# Interface_board.net
KiCad netlist of a schematic drawn in EAGLE
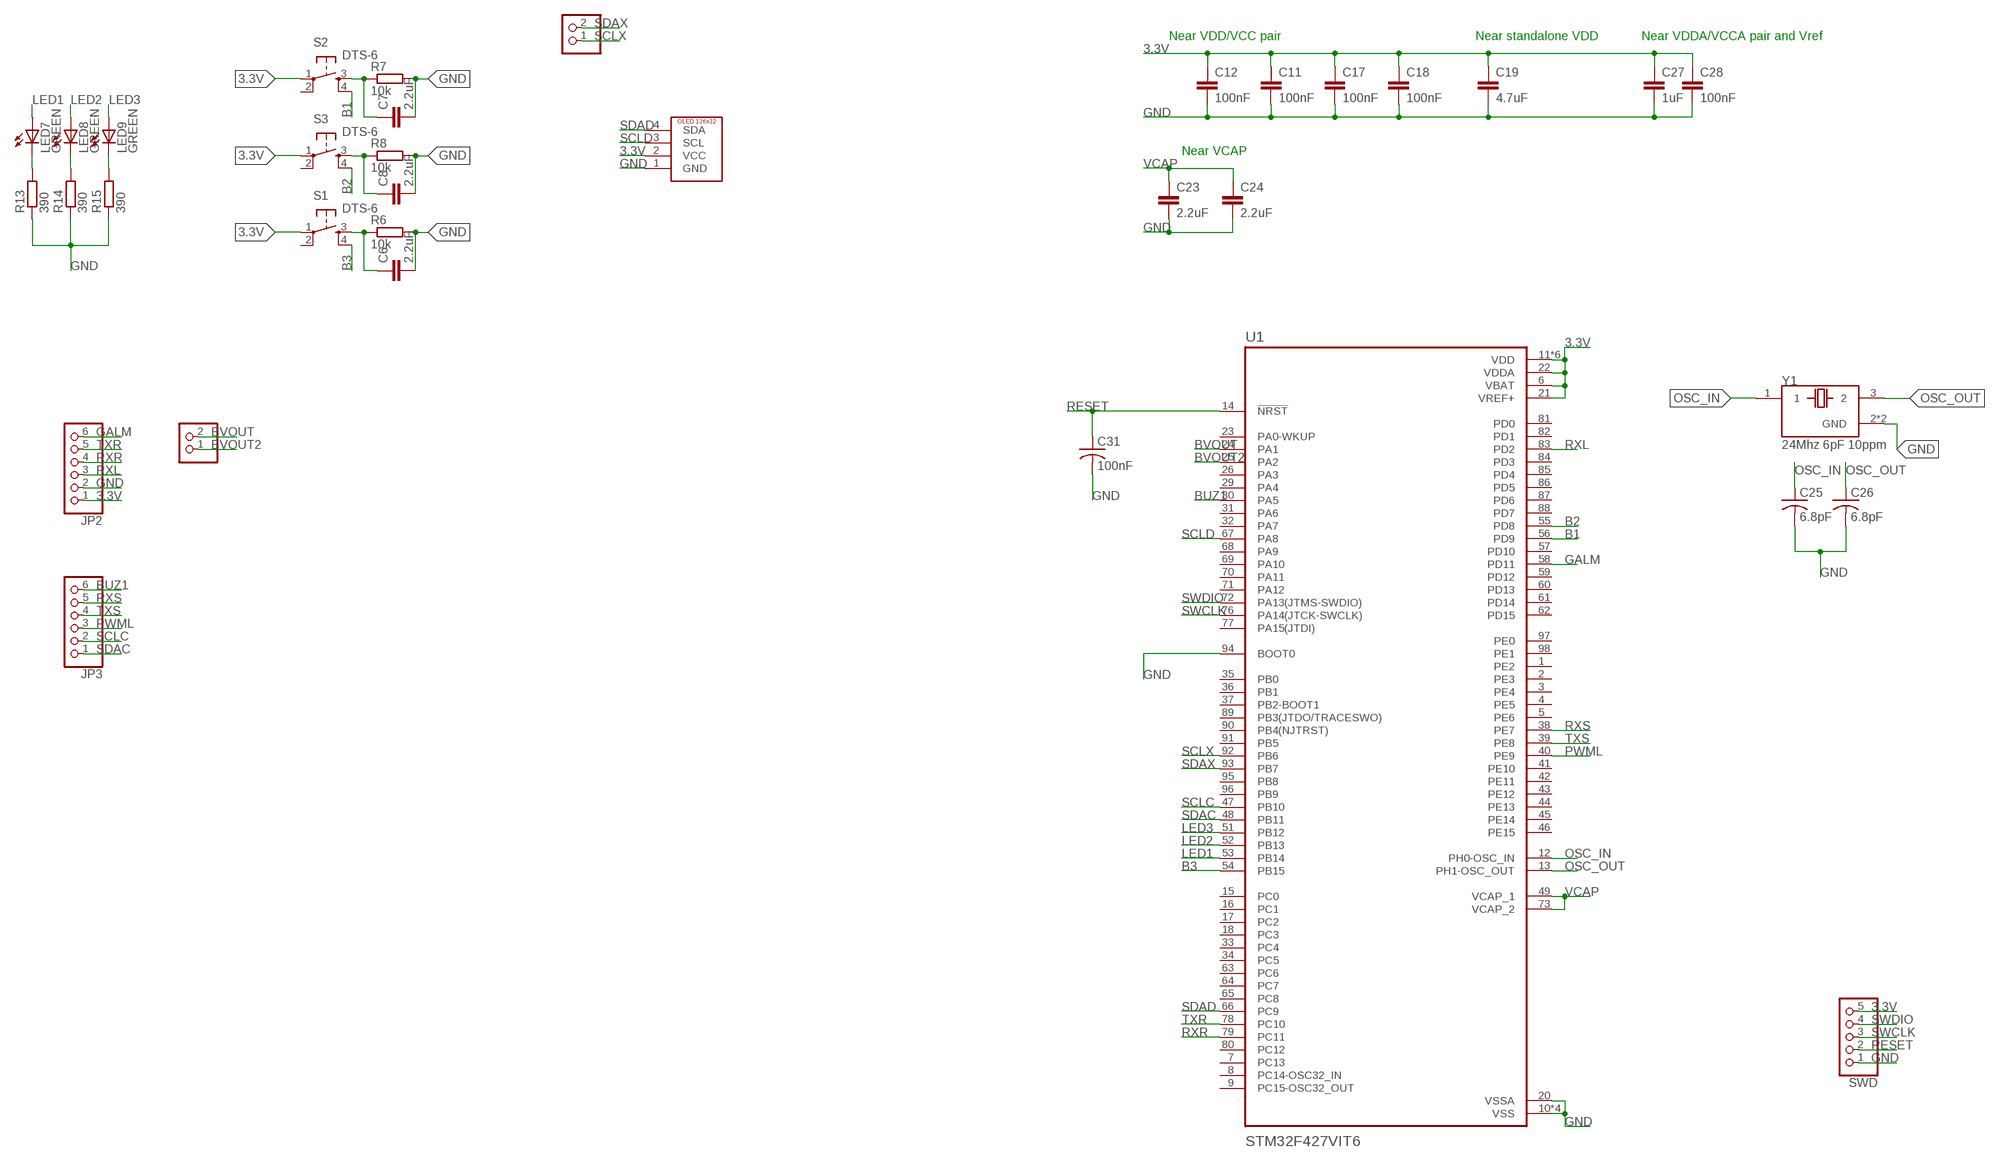
[diagram p0: schematic, sheet 1]

(export (version "E")
  (design (tool "Eeschema 10.0.6"))
  (components
    (comp (ref "C6")
      (value "2.2uF")
      (footprint "eagle-import:C0603")
      (libsource (lib "eagle-import") (part "C-EUC0603"))
    )
    (comp (ref "C7")
      (value "2.2uF")
      (footprint "eagle-import:C0603")
      (libsource (lib "eagle-import") (part "C-EUC0603"))
    )
    (comp (ref "C8")
      (value "2.2uF")
      (footprint "eagle-import:C0603")
      (libsource (lib "eagle-import") (part "C-EUC0603"))
    )
    (comp (ref "C11")
      (value "100nF")
      (footprint "eagle-import:C0603")
      (libsource (lib "eagle-import") (part "C-EUC0603"))
    )
    (comp (ref "C12")
      (value "100nF")
      (footprint "eagle-import:C0603")
      (libsource (lib "eagle-import") (part "C-EUC0603"))
    )
    (comp (ref "C17")
      (value "100nF")
      (footprint "eagle-import:C0603")
      (libsource (lib "eagle-import") (part "C-EUC0603"))
    )
    (comp (ref "C18")
      (value "100nF")
      (footprint "eagle-import:C0603")
      (libsource (lib "eagle-import") (part "C-EUC0603"))
    )
    (comp (ref "C19")
      (value "4.7uF")
      (footprint "eagle-import:C0603")
      (libsource (lib "eagle-import") (part "C-EUC0603"))
    )
    (comp (ref "C23")
      (value "2.2uF")
      (footprint "eagle-import:C0603")
      (libsource (lib "eagle-import") (part "C-EUC0603"))
    )
    (comp (ref "C24")
      (value "2.2uF")
      (footprint "eagle-import:C0603")
      (libsource (lib "eagle-import") (part "C-EUC0603"))
    )
    (comp (ref "C25")
      (value "6.8pF")
      (footprint "eagle-import:C0603")
      (libsource (lib "eagle-import") (part "C-USC0603"))
    )
    (comp (ref "C26")
      (value "6.8pF")
      (footprint "eagle-import:C0603")
      (libsource (lib "eagle-import") (part "C-USC0603"))
    )
    (comp (ref "C27")
      (value "1uF")
      (footprint "eagle-import:C0603")
      (libsource (lib "eagle-import") (part "C-EUC0603"))
    )
    (comp (ref "C28")
      (value "100nF")
      (footprint "eagle-import:C0603")
      (libsource (lib "eagle-import") (part "C-EUC0603"))
    )
    (comp (ref "C31")
      (value "100nF")
      (footprint "eagle-import:C0603")
      (libsource (lib "eagle-import") (part "C-USC0603"))
    )
    (comp (ref "JP1")
      (value "PINHD-1X2")
      (footprint "eagle-import:1X02")
      (libsource (lib "eagle-import") (part "PINHD-1X2"))
    )
    (comp (ref "JP2")
      (value "PINHD-1X6")
      (footprint "eagle-import:1X06")
      (libsource (lib "eagle-import") (part "PINHD-1X6"))
    )
    (comp (ref "JP3")
      (value "PINHD-1X6")
      (footprint "eagle-import:1X06")
      (libsource (lib "eagle-import") (part "PINHD-1X6"))
    )
    (comp (ref "JP4")
      (value "PINHD-1X2")
      (footprint "eagle-import:1X02")
      (libsource (lib "eagle-import") (part "PINHD-1X2"))
    )
    (comp (ref "LED7")
      (value "GREEN")
      (footprint "eagle-import:CHIPLED_0603")
      (libsource (lib "eagle-import") (part "LEDCHIPLED_0603"))
    )
    (comp (ref "LED8")
      (value "GREEN")
      (footprint "eagle-import:CHIPLED_0603")
      (libsource (lib "eagle-import") (part "LEDCHIPLED_0603"))
    )
    (comp (ref "LED9")
      (value "GREEN")
      (footprint "eagle-import:CHIPLED_0603")
      (libsource (lib "eagle-import") (part "LEDCHIPLED_0603"))
    )
    (comp (ref "R6")
      (value "10k")
      (footprint "eagle-import:R0603")
      (libsource (lib "eagle-import") (part "R-EU_R0603"))
    )
    (comp (ref "R7")
      (value "10k")
      (footprint "eagle-import:R0603")
      (libsource (lib "eagle-import") (part "R-EU_R0603"))
    )
    (comp (ref "R8")
      (value "10k")
      (footprint "eagle-import:R0603")
      (libsource (lib "eagle-import") (part "R-EU_R0603"))
    )
    (comp (ref "R13")
      (value "390")
      (footprint "eagle-import:R0603")
      (libsource (lib "eagle-import") (part "R-EU_R0603"))
    )
    (comp (ref "R14")
      (value "390")
      (footprint "eagle-import:R0603")
      (libsource (lib "eagle-import") (part "R-EU_R0603"))
    )
    (comp (ref "R15")
      (value "390")
      (footprint "eagle-import:R0603")
      (libsource (lib "eagle-import") (part "R-EU_R0603"))
    )
    (comp (ref "S1")
      (value "DTS-6")
      (footprint "eagle-import:DTS-6")
      (libsource (lib "eagle-import") (part "DTS-6"))
    )
    (comp (ref "S2")
      (value "DTS-6")
      (footprint "eagle-import:DTS-6")
      (libsource (lib "eagle-import") (part "DTS-6"))
    )
    (comp (ref "S3")
      (value "DTS-6")
      (footprint "eagle-import:DTS-6")
      (libsource (lib "eagle-import") (part "DTS-6"))
    )
    (comp (ref "SWD")
      (value "PINHD-1X5/90")
      (footprint "eagle-import:1X05_90")
      (libsource (lib "eagle-import") (part "PINHD-1X5/90"))
    )
    (comp (ref "U$1")
      (value "OLED126X32THROUGH_HOLE")
      (footprint "eagle-import:OLED128X64")
      (libsource (lib "eagle-import") (part "OLED126X32THROUGH_HOLE"))
    )
    (comp (ref "U1")
      (value "STM32F427VIT6")
      (footprint "eagle-import:QFP50P1600X1600X160-100N")
      (fields (field (name "MF") "STMicroelectronics"))
      (libsource (lib "eagle-import") (part "STM32F427VIT6"))
    )
    (comp (ref "Y1")
      (value "24Mhz 6pF 10ppm")
      (footprint "eagle-import:XTAL_TSX-3225_16.0000MF18X-AC3")
      (fields (field (name "MF") "EPSON") (field (name "MP") "TSX-3225 16.0000MF18X-AC3"))
      (libsource (lib "eagle-import") (part "TSX-3225_16.0000MF18X-AC3"))
    )
  )
  (nets
    (net (code "1") (name "/B1") (class "Default")
      (node (ref "S2") (pin "4") (pinfunction "4_4") (pintype "passive"))
      (node (ref "U1") (pin "56") (pinfunction "PD9_56") (pintype "bidirectional"))
    )
    (net (code "2") (name "/B2") (class "Default")
      (node (ref "S3") (pin "4") (pinfunction "4_4") (pintype "passive"))
      (node (ref "U1") (pin "55") (pinfunction "PD8_55") (pintype "bidirectional"))
    )
    (net (code "3") (name "/B3") (class "Default")
      (node (ref "S1") (pin "4") (pinfunction "4_4") (pintype "passive"))
      (node (ref "U1") (pin "54") (pinfunction "PB15_54") (pintype "bidirectional"))
    )
    (net (code "4") (name "/BUZ1") (class "Default")
      (node (ref "JP3") (pin "6") (pinfunction "6_6") (pintype "passive"))
      (node (ref "U1") (pin "30") (pinfunction "PA5_30") (pintype "bidirectional"))
    )
    (net (code "5") (name "/BVOUT") (class "Default")
      (node (ref "JP4") (pin "2") (pinfunction "2_2") (pintype "passive"))
      (node (ref "U1") (pin "24") (pinfunction "PA1_24") (pintype "bidirectional"))
    )
    (net (code "6") (name "/BVOUT2") (class "Default")
      (node (ref "JP4") (pin "1") (pinfunction "1_1") (pintype "passive"))
      (node (ref "U1") (pin "25") (pinfunction "PA2_25") (pintype "bidirectional"))
    )
    (net (code "7") (name "/GALM") (class "Default")
      (node (ref "JP2") (pin "6") (pinfunction "6_6") (pintype "passive"))
      (node (ref "U1") (pin "58") (pinfunction "PD11_58") (pintype "bidirectional"))
    )
    (net (code "8") (name "/LED1") (class "Default")
      (node (ref "LED7") (pin "A") (pinfunction "A_A") (pintype "passive"))
      (node (ref "U1") (pin "53") (pinfunction "PB14_53") (pintype "bidirectional"))
    )
    (net (code "9") (name "/LED2") (class "Default")
      (node (ref "LED8") (pin "A") (pinfunction "A_A") (pintype "passive"))
      (node (ref "U1") (pin "52") (pinfunction "PB13_52") (pintype "bidirectional"))
    )
    (net (code "10") (name "/LED3") (class "Default")
      (node (ref "LED9") (pin "A") (pinfunction "A_A") (pintype "passive"))
      (node (ref "U1") (pin "51") (pinfunction "PB12_51") (pintype "bidirectional"))
    )
    (net (code "11") (name "/PWML") (class "Default")
      (node (ref "JP3") (pin "3") (pinfunction "3_3") (pintype "passive"))
      (node (ref "U1") (pin "40") (pinfunction "PE9_40") (pintype "bidirectional"))
    )
    (net (code "12") (name "/RESET") (class "Default")
      (node (ref "C31") (pin "1") (pinfunction "1_1") (pintype "passive"))
      (node (ref "SWD") (pin "2") (pinfunction "2_2") (pintype "passive"))
      (node (ref "U1") (pin "14") (pinfunction "~{NRST}_14") (pintype "input"))
    )
    (net (code "13") (name "/RXL") (class "Default")
      (node (ref "JP2") (pin "3") (pinfunction "3_3") (pintype "passive"))
      (node (ref "U1") (pin "83") (pinfunction "PD2_83") (pintype "bidirectional"))
    )
    (net (code "14") (name "/RXR") (class "Default")
      (node (ref "JP2") (pin "4") (pinfunction "4_4") (pintype "passive"))
      (node (ref "U1") (pin "79") (pinfunction "PC11_79") (pintype "bidirectional"))
    )
    (net (code "15") (name "/RXS") (class "Default")
      (node (ref "JP3") (pin "5") (pinfunction "5_5") (pintype "passive"))
      (node (ref "U1") (pin "38") (pinfunction "PE7_38") (pintype "bidirectional"))
    )
    (net (code "16") (name "/SCLC") (class "Default")
      (node (ref "JP3") (pin "2") (pinfunction "2_2") (pintype "passive"))
      (node (ref "U1") (pin "47") (pinfunction "PB10_47") (pintype "bidirectional"))
    )
    (net (code "17") (name "/SCLD") (class "Default")
      (node (ref "U$1") (pin "3") (pinfunction "SCL_3") (pintype "bidirectional"))
      (node (ref "U1") (pin "67") (pinfunction "PA8_67") (pintype "bidirectional"))
    )
    (net (code "18") (name "/SCLX") (class "Default")
      (node (ref "JP1") (pin "1") (pinfunction "1_1") (pintype "passive"))
      (node (ref "U1") (pin "92") (pinfunction "PB6_92") (pintype "bidirectional"))
    )
    (net (code "19") (name "/SDAC") (class "Default")
      (node (ref "JP3") (pin "1") (pinfunction "1_1") (pintype "passive"))
      (node (ref "U1") (pin "48") (pinfunction "PB11_48") (pintype "bidirectional"))
    )
    (net (code "20") (name "/SDAD") (class "Default")
      (node (ref "U$1") (pin "4") (pinfunction "SDA_4") (pintype "bidirectional"))
      (node (ref "U1") (pin "66") (pinfunction "PC9_66") (pintype "bidirectional"))
    )
    (net (code "21") (name "/SDAX") (class "Default")
      (node (ref "JP1") (pin "2") (pinfunction "2_2") (pintype "passive"))
      (node (ref "U1") (pin "93") (pinfunction "PB7_93") (pintype "bidirectional"))
    )
    (net (code "22") (name "/SWCLK") (class "Default")
      (node (ref "SWD") (pin "3") (pinfunction "3_3") (pintype "passive"))
      (node (ref "U1") (pin "76") (pinfunction "PA14(JTCK-SWCLK)_76") (pintype "bidirectional"))
    )
    (net (code "23") (name "/SWDIO") (class "Default")
      (node (ref "SWD") (pin "4") (pinfunction "4_4") (pintype "passive"))
      (node (ref "U1") (pin "72") (pinfunction "PA13(JTMS-SWDIO)_72") (pintype "bidirectional"))
    )
    (net (code "24") (name "/TXR") (class "Default")
      (node (ref "JP2") (pin "5") (pinfunction "5_5") (pintype "passive"))
      (node (ref "U1") (pin "78") (pinfunction "PC10_78") (pintype "bidirectional"))
    )
    (net (code "25") (name "/TXS") (class "Default")
      (node (ref "JP3") (pin "4") (pinfunction "4_4") (pintype "passive"))
      (node (ref "U1") (pin "39") (pinfunction "PE8_39") (pintype "bidirectional"))
    )
    (net (code "26") (name "/VCAP") (class "Default")
      (node (ref "C23") (pin "1") (pinfunction "1_1") (pintype "passive"))
      (node (ref "C24") (pin "1") (pinfunction "1_1") (pintype "passive"))
      (node (ref "U1") (pin "49") (pinfunction "VCAP_1_49") (pintype "passive"))
      (node (ref "U1") (pin "73") (pinfunction "VCAP_2_73") (pintype "passive"))
    )
    (net (code "27") (name "3.3V") (class "Default")
      (node (ref "C11") (pin "1") (pinfunction "1_1") (pintype "passive"))
      (node (ref "C12") (pin "1") (pinfunction "1_1") (pintype "passive"))
      (node (ref "C17") (pin "1") (pinfunction "1_1") (pintype "passive"))
      (node (ref "C18") (pin "1") (pinfunction "1_1") (pintype "passive"))
      (node (ref "C19") (pin "1") (pinfunction "1_1") (pintype "passive"))
      (node (ref "C27") (pin "1") (pinfunction "1_1") (pintype "passive"))
      (node (ref "C28") (pin "1") (pinfunction "1_1") (pintype "passive"))
      (node (ref "JP2") (pin "1") (pinfunction "1_1") (pintype "passive"))
      (node (ref "S1") (pin "1") (pinfunction "1_1") (pintype "passive"))
      (node (ref "S2") (pin "1") (pinfunction "1_1") (pintype "passive"))
      (node (ref "S3") (pin "1") (pinfunction "1_1") (pintype "passive"))
      (node (ref "SWD") (pin "5") (pinfunction "5_5") (pintype "passive"))
      (node (ref "U$1") (pin "2") (pinfunction "VCC_2") (pintype "bidirectional"))
      (node (ref "U1") (pin "100") (pinfunction "VDD_100") (pintype "power_in"))
      (node (ref "U1") (pin "11") (pinfunction "VDD_11") (pintype "power_in"))
      (node (ref "U1") (pin "19") (pinfunction "VDD_19") (pintype "power_in"))
      (node (ref "U1") (pin "21") (pinfunction "VREF+_21") (pintype "power_in"))
      (node (ref "U1") (pin "22") (pinfunction "VDDA_22") (pintype "power_in"))
      (node (ref "U1") (pin "28") (pinfunction "VDD_28") (pintype "power_in"))
      (node (ref "U1") (pin "50") (pinfunction "VDD_50") (pintype "power_in"))
      (node (ref "U1") (pin "6") (pinfunction "VBAT_6") (pintype "power_in"))
      (node (ref "U1") (pin "75") (pinfunction "VDD_75") (pintype "power_in"))
    )
    (net (code "28") (name "GND") (class "Default")
      (node (ref "C11") (pin "2") (pinfunction "2_2") (pintype "passive"))
      (node (ref "C12") (pin "2") (pinfunction "2_2") (pintype "passive"))
      (node (ref "C17") (pin "2") (pinfunction "2_2") (pintype "passive"))
      (node (ref "C18") (pin "2") (pinfunction "2_2") (pintype "passive"))
      (node (ref "C19") (pin "2") (pinfunction "2_2") (pintype "passive"))
      (node (ref "C23") (pin "2") (pinfunction "2_2") (pintype "passive"))
      (node (ref "C24") (pin "2") (pinfunction "2_2") (pintype "passive"))
      (node (ref "C25") (pin "2") (pinfunction "2_2") (pintype "passive"))
      (node (ref "C26") (pin "2") (pinfunction "2_2") (pintype "passive"))
      (node (ref "C27") (pin "2") (pinfunction "2_2") (pintype "passive"))
      (node (ref "C28") (pin "2") (pinfunction "2_2") (pintype "passive"))
      (node (ref "C31") (pin "2") (pinfunction "2_2") (pintype "passive"))
      (node (ref "C6") (pin "2") (pinfunction "2_2") (pintype "passive"))
      (node (ref "C7") (pin "2") (pinfunction "2_2") (pintype "passive"))
      (node (ref "C8") (pin "2") (pinfunction "2_2") (pintype "passive"))
      (node (ref "JP2") (pin "2") (pinfunction "2_2") (pintype "passive"))
      (node (ref "R13") (pin "1") (pinfunction "1_1") (pintype "passive"))
      (node (ref "R14") (pin "1") (pinfunction "1_1") (pintype "passive"))
      (node (ref "R15") (pin "1") (pinfunction "1_1") (pintype "passive"))
      (node (ref "R6") (pin "2") (pinfunction "2_2") (pintype "passive"))
      (node (ref "R7") (pin "2") (pinfunction "2_2") (pintype "passive"))
      (node (ref "R8") (pin "2") (pinfunction "2_2") (pintype "passive"))
      (node (ref "SWD") (pin "1") (pinfunction "1_1") (pintype "passive"))
      (node (ref "U$1") (pin "1") (pinfunction "GND_1") (pintype "bidirectional"))
      (node (ref "U1") (pin "10") (pinfunction "VSS_10") (pintype "power_in"))
      (node (ref "U1") (pin "20") (pinfunction "VSSA_20") (pintype "power_in"))
      (node (ref "U1") (pin "27") (pinfunction "VSS_27") (pintype "power_in"))
      (node (ref "U1") (pin "74") (pinfunction "VSS_74") (pintype "power_in"))
      (node (ref "U1") (pin "94") (pinfunction "BOOT0_94") (pintype "input"))
      (node (ref "U1") (pin "99") (pinfunction "VSS_99") (pintype "power_in"))
      (node (ref "Y1") (pin "2") (pinfunction "GND_2") (pintype "power_in"))
      (node (ref "Y1") (pin "4") (pinfunction "GND_4") (pintype "power_in"))
    )
    (net (code "29") (name "Net-(C6-Pad1)") (class "Default")
      (node (ref "C6") (pin "1") (pinfunction "1_1") (pintype "passive"))
      (node (ref "R6") (pin "1") (pinfunction "1_1") (pintype "passive"))
      (node (ref "S1") (pin "3") (pinfunction "3_3") (pintype "passive"))
    )
    (net (code "30") (name "Net-(C7-Pad1)") (class "Default")
      (node (ref "C7") (pin "1") (pinfunction "1_1") (pintype "passive"))
      (node (ref "R7") (pin "1") (pinfunction "1_1") (pintype "passive"))
      (node (ref "S2") (pin "3") (pinfunction "3_3") (pintype "passive"))
    )
    (net (code "31") (name "Net-(C8-Pad1)") (class "Default")
      (node (ref "C8") (pin "1") (pinfunction "1_1") (pintype "passive"))
      (node (ref "R8") (pin "1") (pinfunction "1_1") (pintype "passive"))
      (node (ref "S3") (pin "3") (pinfunction "3_3") (pintype "passive"))
    )
    (net (code "32") (name "Net-(LED7-PadC)") (class "Default")
      (node (ref "LED7") (pin "C") (pinfunction "C_C") (pintype "passive"))
      (node (ref "R13") (pin "2") (pinfunction "2_2") (pintype "passive"))
    )
    (net (code "33") (name "Net-(LED8-PadC)") (class "Default")
      (node (ref "LED8") (pin "C") (pinfunction "C_C") (pintype "passive"))
      (node (ref "R14") (pin "2") (pinfunction "2_2") (pintype "passive"))
    )
    (net (code "34") (name "Net-(LED9-PadC)") (class "Default")
      (node (ref "LED9") (pin "C") (pinfunction "C_C") (pintype "passive"))
      (node (ref "R15") (pin "2") (pinfunction "2_2") (pintype "passive"))
    )
    (net (code "35") (name "OSC_IN") (class "Default")
      (node (ref "C25") (pin "1") (pinfunction "1_1") (pintype "passive"))
      (node (ref "U1") (pin "12") (pinfunction "PH0-OSC_IN_12") (pintype "bidirectional"))
      (node (ref "Y1") (pin "1") (pinfunction "1_1") (pintype "passive"))
    )
    (net (code "36") (name "OSC_OUT") (class "Default")
      (node (ref "C26") (pin "1") (pinfunction "1_1") (pintype "passive"))
      (node (ref "U1") (pin "13") (pinfunction "PH1-OSC_OUT_13") (pintype "bidirectional"))
      (node (ref "Y1") (pin "3") (pinfunction "2_3") (pintype "passive"))
    )
    (net (code "37") (name "unconnected-(S1-Pad2)") (class "Default")
      (node (ref "S1") (pin "2") (pinfunction "2_2") (pintype "passive"))
    )
    (net (code "38") (name "unconnected-(S2-Pad2)") (class "Default")
      (node (ref "S2") (pin "2") (pinfunction "2_2") (pintype "passive"))
    )
    (net (code "39") (name "unconnected-(S3-Pad2)") (class "Default")
      (node (ref "S3") (pin "2") (pinfunction "2_2") (pintype "passive"))
    )
    (net (code "40") (name "unconnected-(U1-PA0-WKUP-Pad23)") (class "Default")
      (node (ref "U1") (pin "23") (pinfunction "PA0-WKUP_23") (pintype "bidirectional"))
    )
    (net (code "41") (name "unconnected-(U1-PA3-Pad26)") (class "Default")
      (node (ref "U1") (pin "26") (pinfunction "PA3_26") (pintype "bidirectional"))
    )
    (net (code "42") (name "unconnected-(U1-PA4-Pad29)") (class "Default")
      (node (ref "U1") (pin "29") (pinfunction "PA4_29") (pintype "bidirectional"))
    )
    (net (code "43") (name "unconnected-(U1-PA6-Pad31)") (class "Default")
      (node (ref "U1") (pin "31") (pinfunction "PA6_31") (pintype "bidirectional"))
    )
    (net (code "44") (name "unconnected-(U1-PA7-Pad32)") (class "Default")
      (node (ref "U1") (pin "32") (pinfunction "PA7_32") (pintype "bidirectional"))
    )
    (net (code "45") (name "unconnected-(U1-PA9-Pad68)") (class "Default")
      (node (ref "U1") (pin "68") (pinfunction "PA9_68") (pintype "bidirectional"))
    )
    (net (code "46") (name "unconnected-(U1-PA10-Pad69)") (class "Default")
      (node (ref "U1") (pin "69") (pinfunction "PA10_69") (pintype "bidirectional"))
    )
    (net (code "47") (name "unconnected-(U1-PA11-Pad70)") (class "Default")
      (node (ref "U1") (pin "70") (pinfunction "PA11_70") (pintype "bidirectional"))
    )
    (net (code "48") (name "unconnected-(U1-PA12-Pad71)") (class "Default")
      (node (ref "U1") (pin "71") (pinfunction "PA12_71") (pintype "bidirectional"))
    )
    (net (code "49") (name "unconnected-(U1-PA15(JTDI)-Pad77)") (class "Default")
      (node (ref "U1") (pin "77") (pinfunction "PA15(JTDI)_77") (pintype "bidirectional"))
    )
    (net (code "50") (name "unconnected-(U1-PB0-Pad35)") (class "Default")
      (node (ref "U1") (pin "35") (pinfunction "PB0_35") (pintype "bidirectional"))
    )
    (net (code "51") (name "unconnected-(U1-PB1-Pad36)") (class "Default")
      (node (ref "U1") (pin "36") (pinfunction "PB1_36") (pintype "bidirectional"))
    )
    (net (code "52") (name "unconnected-(U1-PB2-BOOT1-Pad37)") (class "Default")
      (node (ref "U1") (pin "37") (pinfunction "PB2-BOOT1_37") (pintype "bidirectional"))
    )
    (net (code "53") (name "unconnected-(U1-PB3(JTDO{slash}TRACESWO)-Pad89)") (class "Default")
      (node (ref "U1") (pin "89") (pinfunction "PB3(JTDO/TRACESWO)_89") (pintype "bidirectional"))
    )
    (net (code "54") (name "unconnected-(U1-PB4(NJTRST)-Pad90)") (class "Default")
      (node (ref "U1") (pin "90") (pinfunction "PB4(NJTRST)_90") (pintype "bidirectional"))
    )
    (net (code "55") (name "unconnected-(U1-PB5-Pad91)") (class "Default")
      (node (ref "U1") (pin "91") (pinfunction "PB5_91") (pintype "bidirectional"))
    )
    (net (code "56") (name "unconnected-(U1-PB8-Pad95)") (class "Default")
      (node (ref "U1") (pin "95") (pinfunction "PB8_95") (pintype "bidirectional"))
    )
    (net (code "57") (name "unconnected-(U1-PB9-Pad96)") (class "Default")
      (node (ref "U1") (pin "96") (pinfunction "PB9_96") (pintype "bidirectional"))
    )
    (net (code "58") (name "unconnected-(U1-PC0-Pad15)") (class "Default")
      (node (ref "U1") (pin "15") (pinfunction "PC0_15") (pintype "bidirectional"))
    )
    (net (code "59") (name "unconnected-(U1-PC1-Pad16)") (class "Default")
      (node (ref "U1") (pin "16") (pinfunction "PC1_16") (pintype "bidirectional"))
    )
    (net (code "60") (name "unconnected-(U1-PC2-Pad17)") (class "Default")
      (node (ref "U1") (pin "17") (pinfunction "PC2_17") (pintype "bidirectional"))
    )
    (net (code "61") (name "unconnected-(U1-PC3-Pad18)") (class "Default")
      (node (ref "U1") (pin "18") (pinfunction "PC3_18") (pintype "bidirectional"))
    )
    (net (code "62") (name "unconnected-(U1-PC4-Pad33)") (class "Default")
      (node (ref "U1") (pin "33") (pinfunction "PC4_33") (pintype "bidirectional"))
    )
    (net (code "63") (name "unconnected-(U1-PC5-Pad34)") (class "Default")
      (node (ref "U1") (pin "34") (pinfunction "PC5_34") (pintype "bidirectional"))
    )
    (net (code "64") (name "unconnected-(U1-PC6-Pad63)") (class "Default")
      (node (ref "U1") (pin "63") (pinfunction "PC6_63") (pintype "bidirectional"))
    )
    (net (code "65") (name "unconnected-(U1-PC7-Pad64)") (class "Default")
      (node (ref "U1") (pin "64") (pinfunction "PC7_64") (pintype "bidirectional"))
    )
    (net (code "66") (name "unconnected-(U1-PC8-Pad65)") (class "Default")
      (node (ref "U1") (pin "65") (pinfunction "PC8_65") (pintype "bidirectional"))
    )
    (net (code "67") (name "unconnected-(U1-PC12-Pad80)") (class "Default")
      (node (ref "U1") (pin "80") (pinfunction "PC12_80") (pintype "bidirectional"))
    )
    (net (code "68") (name "unconnected-(U1-PC13-Pad7)") (class "Default")
      (node (ref "U1") (pin "7") (pinfunction "PC13_7") (pintype "bidirectional"))
    )
    (net (code "69") (name "unconnected-(U1-PC14-OSC32_IN-Pad8)") (class "Default")
      (node (ref "U1") (pin "8") (pinfunction "PC14-OSC32_IN_8") (pintype "bidirectional"))
    )
    (net (code "70") (name "unconnected-(U1-PC15-OSC32_OUT-Pad9)") (class "Default")
      (node (ref "U1") (pin "9") (pinfunction "PC15-OSC32_OUT_9") (pintype "bidirectional"))
    )
    (net (code "71") (name "unconnected-(U1-PD0-Pad81)") (class "Default")
      (node (ref "U1") (pin "81") (pinfunction "PD0_81") (pintype "bidirectional"))
    )
    (net (code "72") (name "unconnected-(U1-PD1-Pad82)") (class "Default")
      (node (ref "U1") (pin "82") (pinfunction "PD1_82") (pintype "bidirectional"))
    )
    (net (code "73") (name "unconnected-(U1-PD3-Pad84)") (class "Default")
      (node (ref "U1") (pin "84") (pinfunction "PD3_84") (pintype "bidirectional"))
    )
    (net (code "74") (name "unconnected-(U1-PD4-Pad85)") (class "Default")
      (node (ref "U1") (pin "85") (pinfunction "PD4_85") (pintype "bidirectional"))
    )
    (net (code "75") (name "unconnected-(U1-PD5-Pad86)") (class "Default")
      (node (ref "U1") (pin "86") (pinfunction "PD5_86") (pintype "bidirectional"))
    )
    (net (code "76") (name "unconnected-(U1-PD6-Pad87)") (class "Default")
      (node (ref "U1") (pin "87") (pinfunction "PD6_87") (pintype "bidirectional"))
    )
    (net (code "77") (name "unconnected-(U1-PD7-Pad88)") (class "Default")
      (node (ref "U1") (pin "88") (pinfunction "PD7_88") (pintype "bidirectional"))
    )
    (net (code "78") (name "unconnected-(U1-PD10-Pad57)") (class "Default")
      (node (ref "U1") (pin "57") (pinfunction "PD10_57") (pintype "bidirectional"))
    )
    (net (code "79") (name "unconnected-(U1-PD12-Pad59)") (class "Default")
      (node (ref "U1") (pin "59") (pinfunction "PD12_59") (pintype "bidirectional"))
    )
    (net (code "80") (name "unconnected-(U1-PD13-Pad60)") (class "Default")
      (node (ref "U1") (pin "60") (pinfunction "PD13_60") (pintype "bidirectional"))
    )
    (net (code "81") (name "unconnected-(U1-PD14-Pad61)") (class "Default")
      (node (ref "U1") (pin "61") (pinfunction "PD14_61") (pintype "bidirectional"))
    )
    (net (code "82") (name "unconnected-(U1-PD15-Pad62)") (class "Default")
      (node (ref "U1") (pin "62") (pinfunction "PD15_62") (pintype "bidirectional"))
    )
    (net (code "83") (name "unconnected-(U1-PE0-Pad97)") (class "Default")
      (node (ref "U1") (pin "97") (pinfunction "PE0_97") (pintype "bidirectional"))
    )
    (net (code "84") (name "unconnected-(U1-PE1-Pad98)") (class "Default")
      (node (ref "U1") (pin "98") (pinfunction "PE1_98") (pintype "bidirectional"))
    )
    (net (code "85") (name "unconnected-(U1-PE2-Pad1)") (class "Default")
      (node (ref "U1") (pin "1") (pinfunction "PE2_1") (pintype "bidirectional"))
    )
    (net (code "86") (name "unconnected-(U1-PE3-Pad2)") (class "Default")
      (node (ref "U1") (pin "2") (pinfunction "PE3_2") (pintype "bidirectional"))
    )
    (net (code "87") (name "unconnected-(U1-PE4-Pad3)") (class "Default")
      (node (ref "U1") (pin "3") (pinfunction "PE4_3") (pintype "bidirectional"))
    )
    (net (code "88") (name "unconnected-(U1-PE5-Pad4)") (class "Default")
      (node (ref "U1") (pin "4") (pinfunction "PE5_4") (pintype "bidirectional"))
    )
    (net (code "89") (name "unconnected-(U1-PE6-Pad5)") (class "Default")
      (node (ref "U1") (pin "5") (pinfunction "PE6_5") (pintype "bidirectional"))
    )
    (net (code "90") (name "unconnected-(U1-PE10-Pad41)") (class "Default")
      (node (ref "U1") (pin "41") (pinfunction "PE10_41") (pintype "bidirectional"))
    )
    (net (code "91") (name "unconnected-(U1-PE11-Pad42)") (class "Default")
      (node (ref "U1") (pin "42") (pinfunction "PE11_42") (pintype "bidirectional"))
    )
    (net (code "92") (name "unconnected-(U1-PE12-Pad43)") (class "Default")
      (node (ref "U1") (pin "43") (pinfunction "PE12_43") (pintype "bidirectional"))
    )
    (net (code "93") (name "unconnected-(U1-PE13-Pad44)") (class "Default")
      (node (ref "U1") (pin "44") (pinfunction "PE13_44") (pintype "bidirectional"))
    )
    (net (code "94") (name "unconnected-(U1-PE14-Pad45)") (class "Default")
      (node (ref "U1") (pin "45") (pinfunction "PE14_45") (pintype "bidirectional"))
    )
    (net (code "95") (name "unconnected-(U1-PE15-Pad46)") (class "Default")
      (node (ref "U1") (pin "46") (pinfunction "PE15_46") (pintype "bidirectional"))
    )
  )
)
